# half-moon-earring.net
KiCad netlist of a schematic drawn in EAGLE
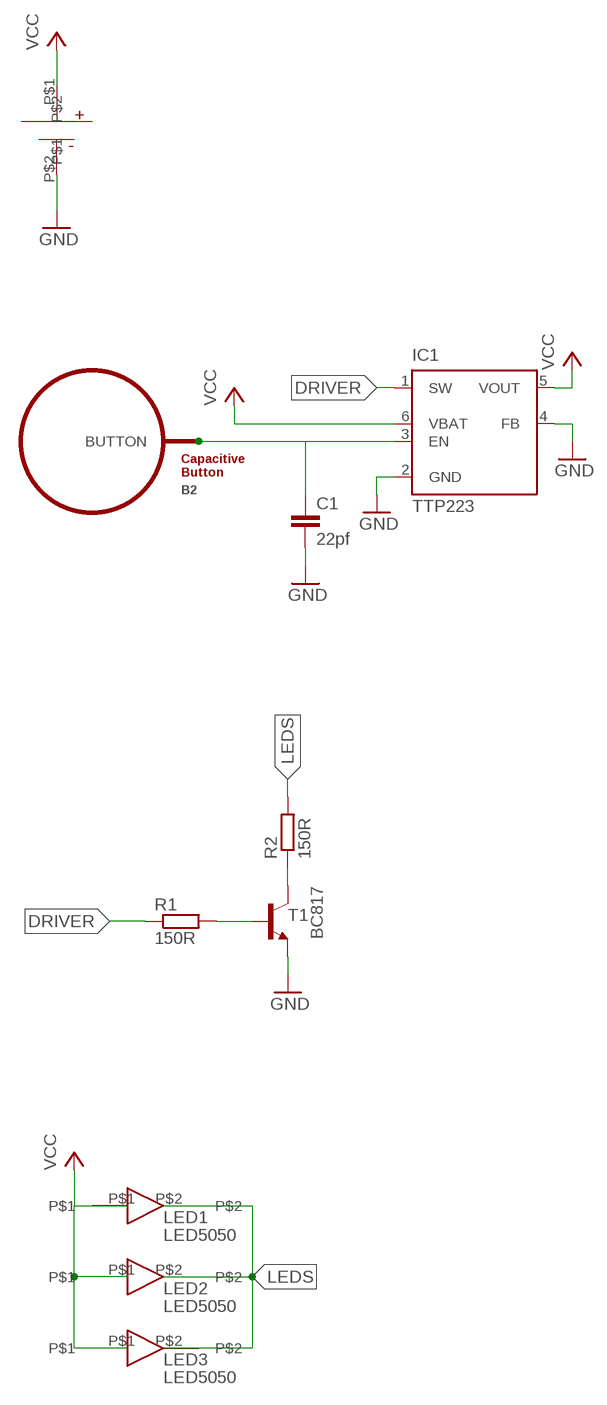
[diagram p0: schematic, sheet 1]

(export (version "E")
  (design (tool "Eeschema 10.0.6"))
  (components
    (comp (ref "B2")
      (value "BUTTON_PASSIVE8MM")
      (footprint "eagle-import:BUTTON_PASSIVE_8MM")
      (libsource (lib "eagle-import") (part "BUTTON_PASSIVE8MM"))
    )
    (comp (ref "C1")
      (value "22pf")
      (footprint "eagle-import:C0805")
      (libsource (lib "eagle-import") (part "C-EUC0805"))
    )
    (comp (ref "IC1")
      (value "TTP223")
      (footprint "eagle-import:TSOT23-6_DDC")
      (fields (field (name "MPN") "TPS61070DDCR"))
      (libsource (lib "eagle-import") (part "TPS6107DDC0"))
    )
    (comp (ref "LED1")
      (value "LED5050")
      (footprint "eagle-import:LED5050")
      (libsource (lib "eagle-import") (part "LED5050"))
    )
    (comp (ref "LED2")
      (value "LED5050")
      (footprint "eagle-import:LED5050")
      (libsource (lib "eagle-import") (part "LED5050"))
    )
    (comp (ref "LED3")
      (value "LED5050")
      (footprint "eagle-import:LED5050")
      (libsource (lib "eagle-import") (part "LED5050"))
    )
    (comp (ref "R1")
      (value "150R")
      (footprint "eagle-import:M0805")
      (libsource (lib "eagle-import") (part "R-EU_M0805"))
    )
    (comp (ref "R2")
      (value "150R")
      (footprint "eagle-import:M0805")
      (libsource (lib "eagle-import") (part "R-EU_M0805"))
    )
    (comp (ref "T1")
      (value "BC817")
      (footprint "eagle-import:SOT23-BEC")
      (libsource (lib "eagle-import") (part "-NPN-SOT23-BECBC817-16LT1"))
    )
    (comp (ref "U$1")
      (value "CR2035")
      (footprint "eagle-import:CR2035")
      (libsource (lib "eagle-import") (part "CR2035"))
    )
  )
  (nets
    (net (code "1") (name "DRIVER") (class "Default")
      (node (ref "IC1") (pin "1") (pinfunction "SW_1") (pintype "input"))
      (node (ref "R1") (pin "1") (pinfunction "1_1") (pintype "passive"))
    )
    (net (code "2") (name "GND") (class "Default")
      (node (ref "C1") (pin "2") (pinfunction "2_2") (pintype "passive"))
      (node (ref "IC1") (pin "2") (pinfunction "GND_2") (pintype "power_in"))
      (node (ref "IC1") (pin "4") (pinfunction "FB_4") (pintype "input"))
      (node (ref "T1") (pin "E") (pinfunction "E_E") (pintype "passive"))
      (node (ref "U$1") (pin "P$2") (pinfunction "P$2_P$2") (pintype "bidirectional"))
    )
    (net (code "3") (name "LEDS") (class "Default")
      (node (ref "LED1") (pin "P$2") (pinfunction "P$2_P$2") (pintype "bidirectional"))
      (node (ref "LED2") (pin "P$2") (pinfunction "P$2_P$2") (pintype "bidirectional"))
      (node (ref "LED3") (pin "P$2") (pinfunction "P$2_P$2") (pintype "bidirectional"))
      (node (ref "R2") (pin "2") (pinfunction "2_2") (pintype "passive"))
    )
    (net (code "4") (name "Net-(IC1-EN)") (class "Default")
      (node (ref "B2") (pin "BUTTON") (pinfunction "BUTTON_BUTTON") (pintype "passive"))
      (node (ref "C1") (pin "1") (pinfunction "1_1") (pintype "passive"))
      (node (ref "IC1") (pin "3") (pinfunction "EN_3") (pintype "input"))
    )
    (net (code "5") (name "Net-(R1-Pad2)") (class "Default")
      (node (ref "R1") (pin "2") (pinfunction "2_2") (pintype "passive"))
      (node (ref "T1") (pin "B") (pinfunction "B_B") (pintype "passive"))
    )
    (net (code "6") (name "Net-(R2-Pad1)") (class "Default")
      (node (ref "R2") (pin "1") (pinfunction "1_1") (pintype "passive"))
      (node (ref "T1") (pin "C") (pinfunction "C_C") (pintype "passive"))
    )
    (net (code "7") (name "VCC") (class "Default")
      (node (ref "IC1") (pin "5") (pinfunction "VOUT_5") (pintype "passive"))
      (node (ref "IC1") (pin "6") (pinfunction "VBAT_6") (pintype "input"))
      (node (ref "LED1") (pin "P$1") (pinfunction "P$1_P$1") (pintype "bidirectional"))
      (node (ref "LED2") (pin "P$1") (pinfunction "P$1_P$1") (pintype "bidirectional"))
      (node (ref "LED3") (pin "P$1") (pinfunction "P$1_P$1") (pintype "bidirectional"))
      (node (ref "U$1") (pin "P$1") (pinfunction "P$1_P$1") (pintype "bidirectional"))
    )
  )
)
